# Pwr.net
KiCad netlist of a schematic drawn in Altium Designer
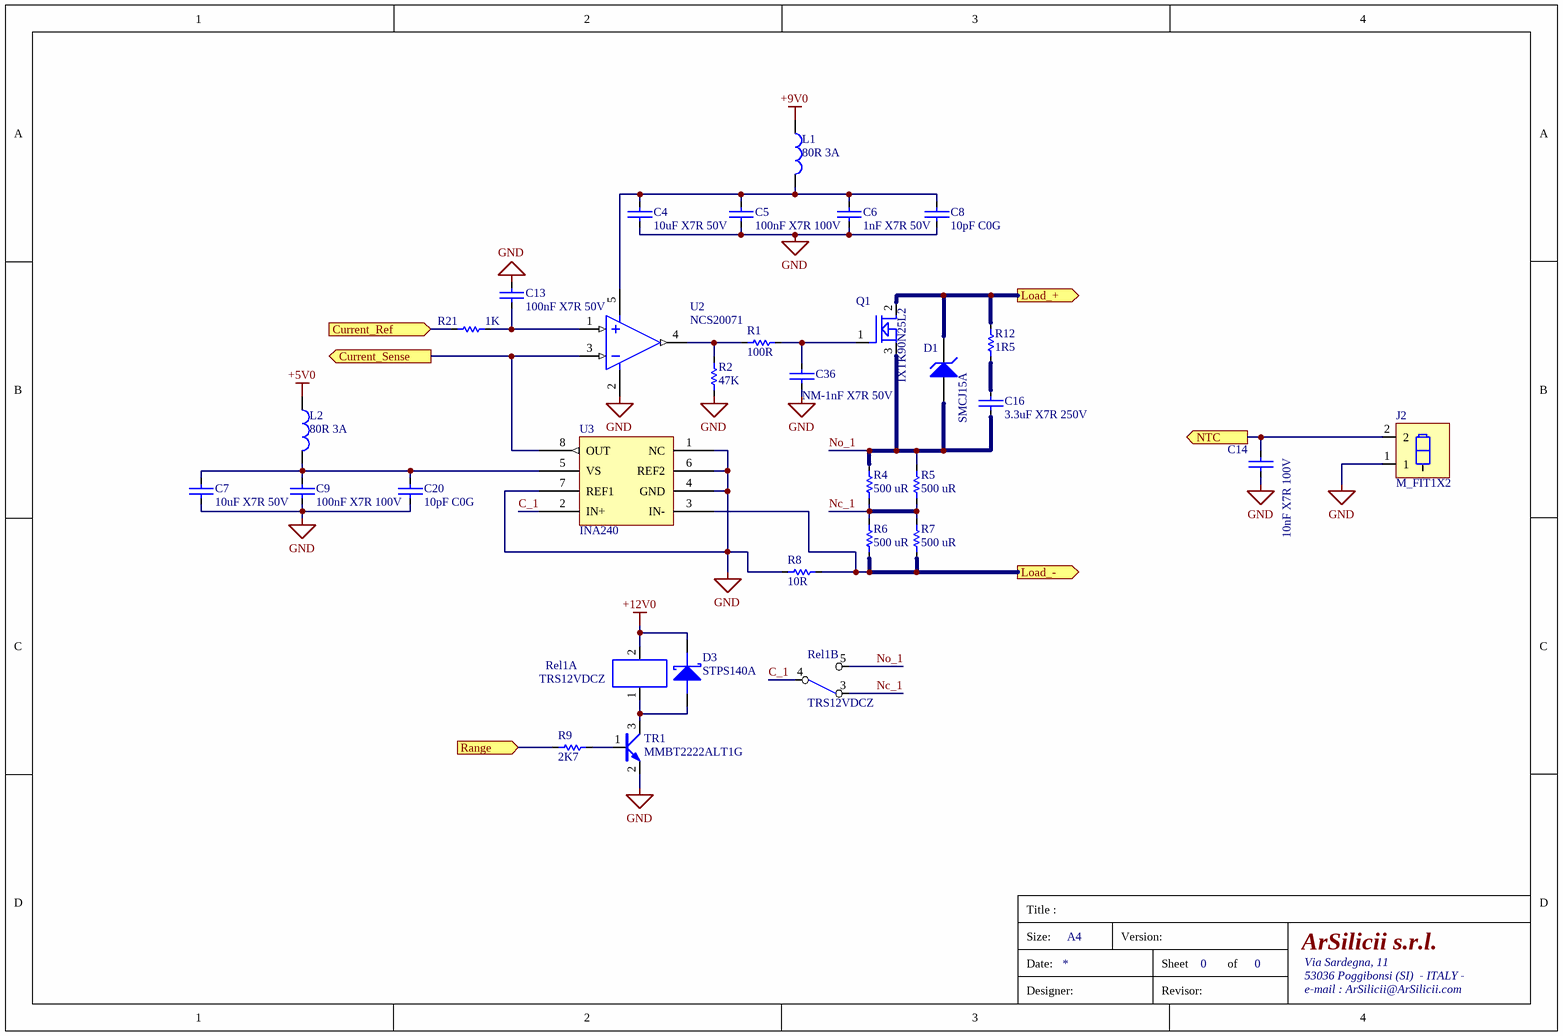
[diagram p0: Pwr.SchDoc]

(export (version "E")
  (design (tool "Eeschema 10.0.6"))
  (components
    (comp (ref "C4")
      (value "10uF X7R 50V")
      (footprint "1206")
      (description "Capacità")
      (fields
        (field (name "1 SUPPLIER PART NUMBER") "CL31B106KBHNNNE")
        (field (name "ARSILICII PART NUMBER") "CPC0232011")
      )
      (libsource (lib "Library_20-02-20") (part "CAP_10uF X7R 50V_1206"))
    )
    (comp (ref "C5")
      (value "100nF X7R 100V")
      (footprint "0805")
      (description "Capacità")
      (fields
        (field (name "1 SUPPLIER PART NUMBER") "CL21B104KCFSFNG")
        (field (name "2 SUPPLIER PART NUMBER") "1907331")
      )
      (libsource (lib "Library_20-02-20") (part "CAP_100nF X7R 100V_0805"))
    )
    (comp (ref "C6")
      (value "1nF X7R 50V")
      (footprint "0603")
      (description "Capacità")
      (fields
        (field (name "1 SUPPLIER PART NUMBER") "CC0603JRX7R9BB102")
        (field (name "ARSILICII PART NUMBER") "CPC0263001")
      )
      (libsource (lib "Library_20-02-20") (part "CAP_1nF X7R 50V_0603"))
    )
    (comp (ref "C7")
      (value "10uF X7R 50V")
      (footprint "1206")
      (description "Capacità")
      (fields
        (field (name "1 SUPPLIER PART NUMBER") "CL31B106KBHNNNE")
        (field (name "ARSILICII PART NUMBER") "CPC0232011")
      )
      (libsource (lib "Library_20-02-20") (part "CAP_10uF X7R 50V_1206"))
    )
    (comp (ref "C8")
      (value "10pF C0G")
      (footprint "0805")
      (description "Capacità")
      (fields (field (name "ARSILICII PART NUMBER") "CPC0614010"))
      (libsource (lib "Library_20-02-20") (part "CAP_10pF C0G_0805"))
    )
    (comp (ref "C9")
      (value "100nF X7R 100V")
      (footprint "0805")
      (description "Capacità")
      (fields
        (field (name "1 SUPPLIER PART NUMBER") "CL21B104KCFSFNG")
        (field (name "2 SUPPLIER PART NUMBER") "1907331")
      )
      (libsource (lib "Library_20-02-20") (part "CAP_100nF X7R 100V_0805"))
    )
    (comp (ref "C13")
      (value "100nF X7R 50V")
      (footprint "0603")
      (description "Capacità")
      (fields
        (field (name "1 SUPPLIER PART NUMBER") "CC0603JRX7R9BB102")
        (field (name "ARSILICII PART NUMBER") "CPC0263001")
      )
      (libsource (lib "Library_20-02-20") (part "CAP_1nF X7R 50V_0603"))
    )
    (comp (ref "C14")
      (value "10nF X7R 100V")
      (footprint "0805")
      (description "Capacità")
      (fields
        (field (name "1 SUPPLIER PART NUMBER") "CL21B104KCFSFNG")
        (field (name "2 SUPPLIER PART NUMBER") "1907331")
      )
      (libsource (lib "Library_20-02-20") (part "CAP_100nF X7R 100V_0805"))
    )
    (comp (ref "C16")
      (value "3.3uF X7R 250V")
      (footprint "2220")
      (description "Capacità")
      (fields
        (field (name "1 SUPPLIER PART NUMBER") "2435506")
        (field (name "2 SUPPLIER PART NUMBER") "810-CGA9N3X7R2E105K")
      )
      (libsource (lib "Library_20-02-20") (part "CAP_1uF X7R 250V_2220"))
    )
    (comp (ref "C20")
      (value "10pF C0G")
      (footprint "0805")
      (description "Capacità")
      (fields (field (name "ARSILICII PART NUMBER") "CPC0614010"))
      (libsource (lib "Library_20-02-20") (part "CAP_10pF C0G_0805"))
    )
    (comp (ref "C36")
      (value "NM-1nF X7R 50V")
      (footprint "0603")
      (description "Capacità")
      (fields
        (field (name "1 SUPPLIER PART NUMBER") "CC0603JRX7R9BB102")
        (field (name "ARSILICII PART NUMBER") "CPC0263001")
      )
      (libsource (lib "Library_20-02-20") (part "CAP_1nF X7R 50V_0603"))
    )
    (comp (ref "D1")
      (value "SMCJ15A")
      (footprint "LFUS-DO-214AB-2_V")
      (fields (field (name "MANUFACTURER") "Littelfuse"))
      (libsource (lib "Altium Content Vault") (part "DZEN-AK-2"))
    )
    (comp (ref "D3")
      (value "STPS140A")
      (footprint "SMA")
      (description "Diodo Schottky")
      (fields
        (field (name "MANUFACTURER") "STMicroelectronics")
        (field (name "1 SUPPLIER PART NUMBER") "STMSTPS140A")
      )
      (libsource (lib "Library_20-02-20") (part "DIODE SCHOTTKY_STPS140A"))
    )
    (comp (ref "J2")
      (value "M_FIT1X2")
      (footprint "M_FIT_JR1X2V")
      (description "Mini Fit Junior 2 poli")
      (fields (field (name "ARSILICII PART NUMBER") "QA02006000") (field (name "MANUFACTURER") "Molex"))
      (libsource (lib "Library_20-02-20") (part "M_FIT1X2"))
    )
    (comp (ref "L1")
      (value "80R 3A")
      (footprint "1206")
      (description "Ferrite")
      (fields
        (field (name "1 SUPPLIER PART NUMBER") "3275550P")
        (field (name "ARSILICII PART NUMBER") "CPF0006000")
      )
      (libsource (lib "Library_20-02-20") (part "Ferrite 80R 3A"))
    )
    (comp (ref "L2")
      (value "80R 3A")
      (footprint "1206")
      (description "Ferrite")
      (fields
        (field (name "1 SUPPLIER PART NUMBER") "3275550P")
        (field (name "ARSILICII PART NUMBER") "CPF0006000")
      )
      (libsource (lib "Library_20-02-20") (part "Ferrite 80R 3A"))
    )
    (comp (ref "Q1")
      (value "IXTK90N25L2")
      (footprint "PLUS-247")
      (description "MOS CANALE N-250V-90A Linear")
      (fields
        (field (name "1 SUPPLIER PART NUMBER") "PB90N06S4-04")
        (field (name "2 SUPPLIER PART NUMBER") "826-9042P")
      )
      (libsource (lib "Library_20-02-20") (part "IXTK90N25L2"))
    )
    (comp (ref "R1")
      (value "100R")
      (footprint "0805")
      (description "Resistenza")
      (libsource (lib "Library_20-02-20") (part "RES_SMD"))
    )
    (comp (ref "R2")
      (value "47K")
      (footprint "0805")
      (description "Resistenza")
      (libsource (lib "Library_20-02-20") (part "RES_SMD"))
    )
    (comp (ref "R4")
      (value "500 uR")
      (footprint "2512")
      (description "Resistenza")
      (libsource (lib "Library_20-02-20") (part "RES_SMD"))
    )
    (comp (ref "R5")
      (value "500 uR")
      (footprint "2512")
      (description "Resistenza")
      (libsource (lib "Library_20-02-20") (part "RES_SMD"))
    )
    (comp (ref "R6")
      (value "500 uR")
      (footprint "2512")
      (description "Resistenza")
      (libsource (lib "Library_20-02-20") (part "RES_SMD"))
    )
    (comp (ref "R7")
      (value "500 uR")
      (footprint "2512")
      (description "Resistenza")
      (libsource (lib "Library_20-02-20") (part "RES_SMD"))
    )
    (comp (ref "R8")
      (value "10R")
      (footprint "1206")
      (description "Resistenza")
      (libsource (lib "Library_20-02-20") (part "RES_SMD"))
    )
    (comp (ref "R9")
      (value "2K7")
      (footprint "0805")
      (description "Resistenza")
      (libsource (lib "Library_20-02-20") (part "RES_SMD"))
    )
    (comp (ref "R12")
      (value "1R5")
      (footprint "2512")
      (description "Resistenza")
      (libsource (lib "Library_20-02-20") (part "RES_SMD"))
    )
    (comp (ref "R21")
      (value "1K")
      (footprint "0805")
      (description "Resistenza")
      (libsource (lib "Library_20-02-20") (part "RES_SMD"))
    )
    (comp (ref "Rel1")
      (value "TRS12VDCZ")
      (footprint "RELE_TRS")
      (description "Relay")
      (fields
        (field (name "2 SUPPLIER PART NUMBER") "FRS3M C-S DC12V")
        (field (name "3 SUPPLIER PART NUMBER") "R504D/012Z1F")
      )
      (libsource (lib "Library_20-02-20") (part "RELE'_TRS12VDCZ"))
    )
    (comp (ref "TR1")
      (value "MMBT2222ALT1G")
      (footprint "SOT-23")
      (description "NPN Transistor")
      (fields
        (field (name "1 SUPPLIER PART NUMBER") "SCGMMBT2222ALT1G")
        (field (name "2 SUPPLIER PART NUMBER") "1459098")
      )
      (libsource (lib "Library_20-02-20") (part "NPN_MMBT2222ALT1G"))
    )
    (comp (ref "U2")
      (value "NCS20071")
      (footprint "SOT-553-5")
      (description "Rail-to-Rail Input/Output, 3 MHz Op Amps")
      (fields
        (field (name "1 SUPPLIER PART NUMBER") "MCP6021-E/SN-ND")
        (field (name "MANUFACTURER") "Microchip Technology")
      )
      (libsource (lib "Library_20-02-20") (part "NCS20071"))
    )
    (comp (ref "U3")
      (value "INA240")
      (footprint "TSSOP-8")
      (description "Current sense amplifier")
      (libsource (lib "Library_20-02-20") (part "INA240"))
    )
  )
  (nets
    (net (code "1") (name "+5V0") (class "Default")
      (node (ref "L2") (pin "1") (pinfunction "1_1") (pintype "passive"))
    )
    (net (code "2") (name "+9V0") (class "Default")
      (node (ref "L1") (pin "1") (pinfunction "1_1") (pintype "passive"))
    )
    (net (code "3") (name "+12V0") (class "Default")
      (node (ref "D3") (pin "K") (pinfunction "K_K") (pintype "passive"))
      (node (ref "Rel1") (pin "2") (pintype "passive"))
    )
    (net (code "4") (name "/C_1") (class "Default")
      (node (ref "Rel1") (pin "4") (pintype "passive"))
      (node (ref "U3") (pin "2") (pinfunction "IN+_2") (pintype "tri_state"))
    )
    (net (code "5") (name "/Current_Ref") (class "Default")
      (node (ref "R21") (pin "1") (pinfunction "1_1") (pintype "passive"))
    )
    (net (code "6") (name "/Current_Sense") (class "Default")
      (node (ref "U2") (pin "3") (pintype "input"))
      (node (ref "U3") (pin "8") (pinfunction "OUT_8") (pintype "output"))
    )
    (net (code "7") (name "/Load_+") (class "Default")
      (node (ref "D1") (pin "2") (pinfunction "K_2") (pintype "passive"))
      (node (ref "Q1") (pin "2") (pinfunction "DRAIN_2") (pintype "passive"))
      (node (ref "R12") (pin "1") (pinfunction "1_1") (pintype "passive"))
    )
    (net (code "8") (name "/Load_-") (class "Default")
      (node (ref "R6") (pin "2") (pinfunction "2_2") (pintype "passive"))
      (node (ref "R7") (pin "2") (pinfunction "2_2") (pintype "passive"))
      (node (ref "R8") (pin "1") (pinfunction "1_1") (pintype "passive"))
      (node (ref "U3") (pin "3") (pinfunction "IN-_3") (pintype "tri_state"))
    )
    (net (code "9") (name "/NTC") (class "Default")
      (node (ref "C14") (pin "1") (pintype "passive"))
      (node (ref "J2") (pin "2") (pinfunction "2_2") (pintype "passive"))
    )
    (net (code "10") (name "/Nc_1") (class "Default")
      (node (ref "R4") (pin "2") (pinfunction "2_2") (pintype "passive"))
      (node (ref "R5") (pin "2") (pinfunction "2_2") (pintype "passive"))
      (node (ref "R6") (pin "1") (pinfunction "1_1") (pintype "passive"))
      (node (ref "R7") (pin "1") (pinfunction "1_1") (pintype "passive"))
      (node (ref "Rel1") (pin "3") (pintype "passive"))
    )
    (net (code "11") (name "/No_1") (class "Default")
      (node (ref "C16") (pin "2") (pintype "passive"))
      (node (ref "D1") (pin "1") (pinfunction "A_1") (pintype "passive"))
      (node (ref "Q1") (pin "3") (pinfunction "SOURCE_3") (pintype "passive"))
      (node (ref "R4") (pin "1") (pinfunction "1_1") (pintype "passive"))
      (node (ref "R5") (pin "1") (pinfunction "1_1") (pintype "passive"))
      (node (ref "Rel1") (pin "5") (pintype "passive"))
    )
    (net (code "12") (name "/Range") (class "Default")
      (node (ref "R9") (pin "2") (pinfunction "2_2") (pintype "passive"))
    )
    (net (code "13") (name "GND") (class "Default")
      (node (ref "C13") (pin "2") (pintype "passive"))
      (node (ref "C14") (pin "2") (pintype "passive"))
      (node (ref "C20") (pin "2") (pintype "passive"))
      (node (ref "C36") (pin "1") (pintype "passive"))
      (node (ref "C4") (pin "2") (pintype "passive"))
      (node (ref "C5") (pin "2") (pintype "passive"))
      (node (ref "C6") (pin "2") (pintype "passive"))
      (node (ref "C7") (pin "2") (pintype "passive"))
      (node (ref "C8") (pin "2") (pintype "passive"))
      (node (ref "C9") (pin "2") (pintype "passive"))
      (node (ref "J2") (pin "1") (pinfunction "1_1") (pintype "passive"))
      (node (ref "R2") (pin "2") (pinfunction "2_2") (pintype "passive"))
      (node (ref "R8") (pin "2") (pinfunction "2_2") (pintype "passive"))
      (node (ref "TR1") (pin "2") (pinfunction "E_2") (pintype "passive"))
      (node (ref "U2") (pin "2") (pintype "power_in"))
      (node (ref "U3") (pin "1") (pinfunction "NC_1") (pintype "passive"))
      (node (ref "U3") (pin "4") (pinfunction "GND_4") (pintype "power_in"))
      (node (ref "U3") (pin "6") (pinfunction "REF2_6") (pintype "passive"))
      (node (ref "U3") (pin "7") (pinfunction "REF1_7") (pintype "passive"))
    )
    (net (code "14") (name "Net-(C4-Pad1)") (class "Default")
      (node (ref "C4") (pin "1") (pintype "passive"))
      (node (ref "C5") (pin "1") (pintype "passive"))
      (node (ref "C6") (pin "1") (pintype "passive"))
      (node (ref "C8") (pin "1") (pintype "passive"))
      (node (ref "L1") (pin "2") (pinfunction "2_2") (pintype "passive"))
      (node (ref "U2") (pin "5") (pintype "power_in"))
    )
    (net (code "15") (name "Net-(C13-Pad1)") (class "Default")
      (node (ref "C13") (pin "1") (pintype "passive"))
      (node (ref "R21") (pin "2") (pinfunction "2_2") (pintype "passive"))
      (node (ref "U2") (pin "1") (pintype "input"))
    )
    (net (code "16") (name "Net-(C16-Pad1)") (class "Default")
      (node (ref "C16") (pin "1") (pintype "passive"))
      (node (ref "R12") (pin "2") (pinfunction "2_2") (pintype "passive"))
    )
    (net (code "17") (name "Net-(Q1-GATE)") (class "Default")
      (node (ref "C36") (pin "2") (pintype "passive"))
      (node (ref "Q1") (pin "1") (pinfunction "GATE_1") (pintype "passive"))
      (node (ref "R1") (pin "2") (pinfunction "2_2") (pintype "passive"))
    )
    (net (code "18") (name "Net-(R1-Pad1)") (class "Default")
      (node (ref "R1") (pin "1") (pinfunction "1_1") (pintype "passive"))
      (node (ref "R2") (pin "1") (pinfunction "1_1") (pintype "passive"))
      (node (ref "U2") (pin "4") (pintype "output"))
    )
    (net (code "19") (name "Net-(TR1-B)") (class "Default")
      (node (ref "R9") (pin "1") (pinfunction "1_1") (pintype "passive"))
      (node (ref "TR1") (pin "1") (pinfunction "B_1") (pintype "passive"))
    )
    (net (code "20") (name "Net-(TR1-C)") (class "Default")
      (node (ref "D3") (pin "A") (pinfunction "A_A") (pintype "passive"))
      (node (ref "Rel1") (pin "1") (pintype "passive"))
      (node (ref "TR1") (pin "3") (pinfunction "C_3") (pintype "passive"))
    )
    (net (code "21") (name "Net-(U3-VS)") (class "Default")
      (node (ref "C20") (pin "1") (pintype "passive"))
      (node (ref "C7") (pin "1") (pintype "passive"))
      (node (ref "C9") (pin "1") (pintype "passive"))
      (node (ref "L2") (pin "2") (pinfunction "2_2") (pintype "passive"))
      (node (ref "U3") (pin "5") (pinfunction "VS_5") (pintype "power_in"))
    )
  )
)
